# FAIO2.net
KiCad netlist of a schematic drawn in EAGLE
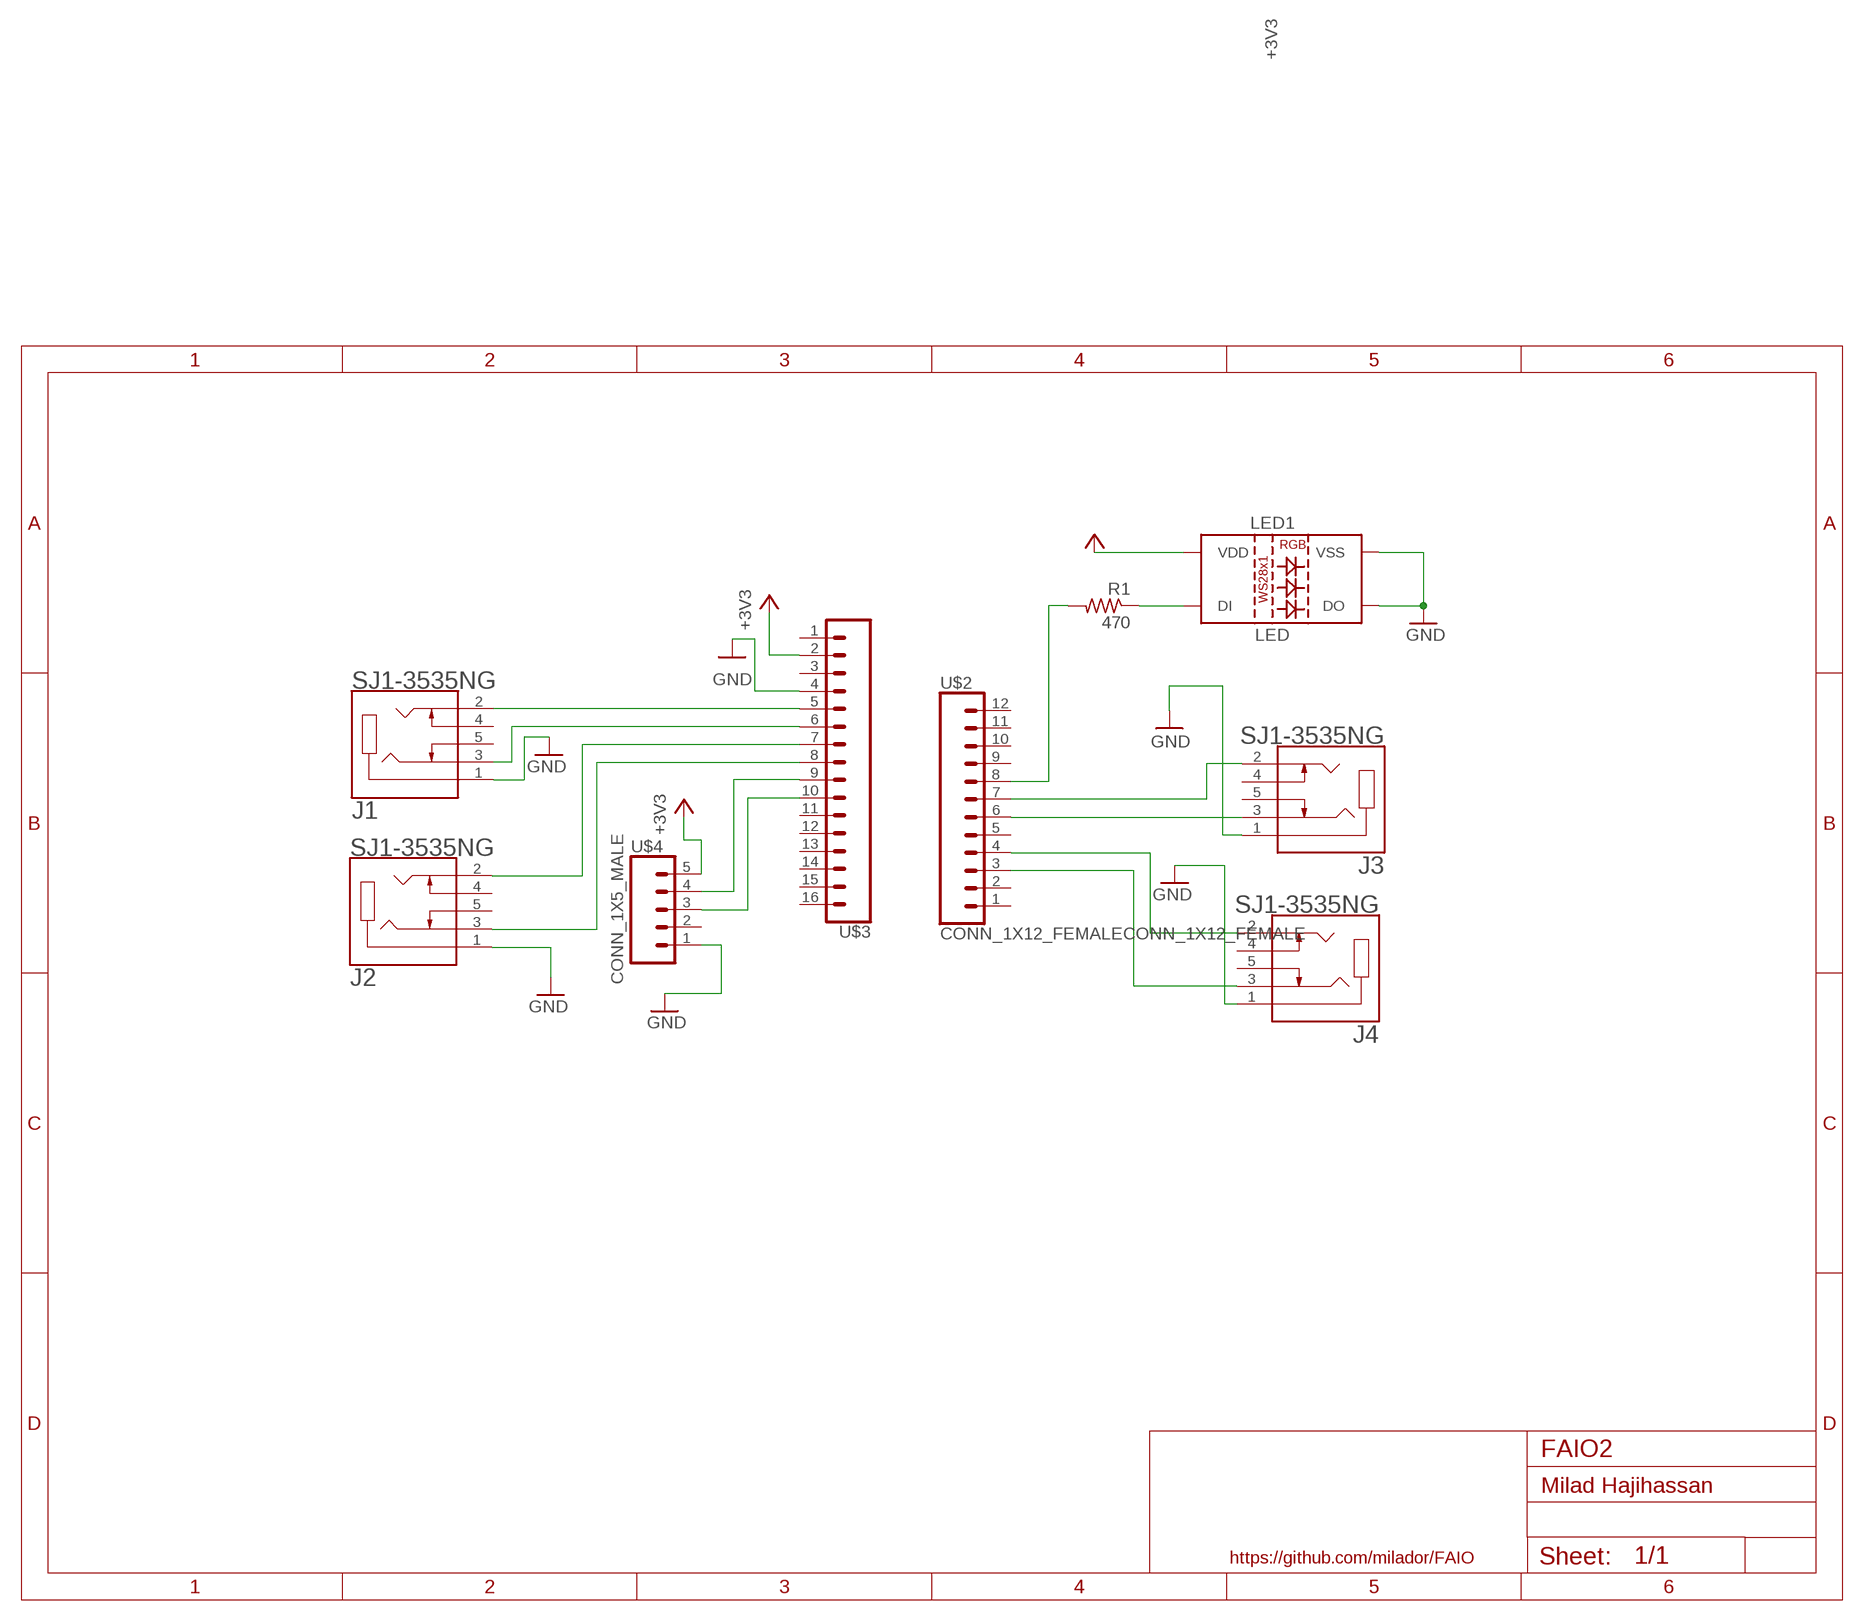
[diagram p0: schematic, sheet 1]

(export (version "E")
  (design (tool "Eeschema 10.0.6"))
  (components
    (comp (ref "J1")
      (value "SJ1-3535NG")
      (footprint "eagle-import:CUI_SJ1-3535NG")
      (fields (field (name "MANUFACTURER") "CUI"))
      (libsource (lib "eagle-import") (part "SJ1-3535NG"))
    )
    (comp (ref "J2")
      (value "SJ1-3535NG")
      (footprint "eagle-import:CUI_SJ1-3535NG")
      (fields (field (name "MANUFACTURER") "CUI"))
      (libsource (lib "eagle-import") (part "SJ1-3535NG"))
    )
    (comp (ref "J3")
      (value "SJ1-3535NG")
      (footprint "eagle-import:CUI_SJ1-3535NG")
      (fields (field (name "MANUFACTURER") "CUI"))
      (libsource (lib "eagle-import") (part "SJ1-3535NG"))
    )
    (comp (ref "J4")
      (value "SJ1-3535NG")
      (footprint "eagle-import:CUI_SJ1-3535NG")
      (fields (field (name "MANUFACTURER") "CUI"))
      (libsource (lib "eagle-import") (part "SJ1-3535NG"))
    )
    (comp (ref "LED1")
      (value "LED")
      (footprint "eagle-import:NEOPIXELS-5MM")
      (libsource (lib "eagle-import") (part "NEOPIXELS-5MM"))
    )
    (comp (ref "R1")
      (value "470")
      (footprint "eagle-import:0204_7")
      (libsource (lib "eagle-import") (part "R-US_0204/7"))
    )
    (comp (ref "U$2")
      (value "CONN_1X12_FEMALECONN_1X12_FEMALE")
      (footprint "eagle-import:CONN_1X12")
      (libsource (lib "eagle-import") (part "CONN_1X12_FEMALECONN_1X12_FEMALE"))
    )
    (comp (ref "U$3")
      (value "CONN_1X16_FEMALECONN_1X16_FEMALE")
      (footprint "eagle-import:CONN_1X16")
      (libsource (lib "eagle-import") (part "CONN_1X16_FEMALECONN_1X16_FEMALE"))
    )
    (comp (ref "U$4")
      (value "CONN_1X5_MALE")
      (footprint "eagle-import:CONN_1X5")
      (libsource (lib "eagle-import") (part "CONN_1X5_MALE"))
    )
  )
  (nets
    (net (code "1") (name "+3V3") (class "Default")
      (node (ref "LED1") (pin "2") (pinfunction "VDD_2") (pintype "bidirectional"))
      (node (ref "U$3") (pin "2") (pinfunction "2_2") (pintype "passive"))
      (node (ref "U$4") (pin "5") (pinfunction "5_5") (pintype "passive"))
    )
    (net (code "2") (name "GND") (class "Default")
      (node (ref "J1") (pin "1") (pinfunction "1_1") (pintype "passive"))
      (node (ref "J2") (pin "1") (pinfunction "1_1") (pintype "passive"))
      (node (ref "J3") (pin "1") (pinfunction "1_1") (pintype "passive"))
      (node (ref "J4") (pin "1") (pinfunction "1_1") (pintype "passive"))
      (node (ref "LED1") (pin "3") (pinfunction "VSS_3") (pintype "bidirectional"))
      (node (ref "LED1") (pin "4") (pinfunction "DO_4") (pintype "bidirectional"))
      (node (ref "U$3") (pin "4") (pinfunction "4_4") (pintype "passive"))
      (node (ref "U$4") (pin "1") (pinfunction "1_1") (pintype "passive"))
    )
    (net (code "3") (name "Net-(J1-Pad2)") (class "Default")
      (node (ref "J1") (pin "2") (pinfunction "2_2") (pintype "passive"))
      (node (ref "U$3") (pin "5") (pinfunction "5_5") (pintype "passive"))
    )
    (net (code "4") (name "Net-(J1-Pad3)") (class "Default")
      (node (ref "J1") (pin "3") (pinfunction "3_3") (pintype "passive"))
      (node (ref "U$3") (pin "6") (pinfunction "6_6") (pintype "passive"))
    )
    (net (code "5") (name "Net-(J2-Pad2)") (class "Default")
      (node (ref "J2") (pin "2") (pinfunction "2_2") (pintype "passive"))
      (node (ref "U$3") (pin "7") (pinfunction "7_7") (pintype "passive"))
    )
    (net (code "6") (name "Net-(J2-Pad3)") (class "Default")
      (node (ref "J2") (pin "3") (pinfunction "3_3") (pintype "passive"))
      (node (ref "U$3") (pin "8") (pinfunction "8_8") (pintype "passive"))
    )
    (net (code "7") (name "Net-(J3-Pad2)") (class "Default")
      (node (ref "J3") (pin "2") (pinfunction "2_2") (pintype "passive"))
      (node (ref "U$2") (pin "7") (pinfunction "7_7") (pintype "passive"))
    )
    (net (code "8") (name "Net-(J3-Pad3)") (class "Default")
      (node (ref "J3") (pin "3") (pinfunction "3_3") (pintype "passive"))
      (node (ref "U$2") (pin "6") (pinfunction "6_6") (pintype "passive"))
    )
    (net (code "9") (name "Net-(J4-Pad2)") (class "Default")
      (node (ref "J4") (pin "2") (pinfunction "2_2") (pintype "passive"))
      (node (ref "U$2") (pin "4") (pinfunction "4_4") (pintype "passive"))
    )
    (net (code "10") (name "Net-(J4-Pad3)") (class "Default")
      (node (ref "J4") (pin "3") (pinfunction "3_3") (pintype "passive"))
      (node (ref "U$2") (pin "3") (pinfunction "3_3") (pintype "passive"))
    )
    (net (code "11") (name "Net-(LED1-DI)") (class "Default")
      (node (ref "LED1") (pin "1") (pinfunction "DI_1") (pintype "bidirectional"))
      (node (ref "R1") (pin "1") (pinfunction "1_1") (pintype "passive"))
    )
    (net (code "12") (name "Net-(R1-Pad2)") (class "Default")
      (node (ref "R1") (pin "2") (pinfunction "2_2") (pintype "passive"))
      (node (ref "U$2") (pin "8") (pinfunction "8_8") (pintype "passive"))
    )
    (net (code "13") (name "Net-(U$3-Pad9)") (class "Default")
      (node (ref "U$3") (pin "9") (pinfunction "9_9") (pintype "passive"))
      (node (ref "U$4") (pin "4") (pinfunction "4_4") (pintype "passive"))
    )
    (net (code "14") (name "Net-(U$3-Pad10)") (class "Default")
      (node (ref "U$3") (pin "10") (pinfunction "10_10") (pintype "passive"))
      (node (ref "U$4") (pin "3") (pinfunction "3_3") (pintype "passive"))
    )
    (net (code "15") (name "unconnected-(J1-Pad4)") (class "Default")
      (node (ref "J1") (pin "4") (pinfunction "4_4") (pintype "passive"))
    )
    (net (code "16") (name "unconnected-(J1-Pad5)") (class "Default")
      (node (ref "J1") (pin "5") (pinfunction "5_5") (pintype "passive"))
    )
    (net (code "17") (name "unconnected-(J2-Pad4)") (class "Default")
      (node (ref "J2") (pin "4") (pinfunction "4_4") (pintype "passive"))
    )
    (net (code "18") (name "unconnected-(J2-Pad5)") (class "Default")
      (node (ref "J2") (pin "5") (pinfunction "5_5") (pintype "passive"))
    )
    (net (code "19") (name "unconnected-(J3-Pad4)") (class "Default")
      (node (ref "J3") (pin "4") (pinfunction "4_4") (pintype "passive"))
    )
    (net (code "20") (name "unconnected-(J3-Pad5)") (class "Default")
      (node (ref "J3") (pin "5") (pinfunction "5_5") (pintype "passive"))
    )
    (net (code "21") (name "unconnected-(J4-Pad4)") (class "Default")
      (node (ref "J4") (pin "4") (pinfunction "4_4") (pintype "passive"))
    )
    (net (code "22") (name "unconnected-(J4-Pad5)") (class "Default")
      (node (ref "J4") (pin "5") (pinfunction "5_5") (pintype "passive"))
    )
    (net (code "23") (name "unconnected-(U$2-Pad1)") (class "Default")
      (node (ref "U$2") (pin "1") (pinfunction "1_1") (pintype "passive"))
    )
    (net (code "24") (name "unconnected-(U$2-Pad2)") (class "Default")
      (node (ref "U$2") (pin "2") (pinfunction "2_2") (pintype "passive"))
    )
    (net (code "25") (name "unconnected-(U$2-Pad5)") (class "Default")
      (node (ref "U$2") (pin "5") (pinfunction "5_5") (pintype "passive"))
    )
    (net (code "26") (name "unconnected-(U$2-Pad9)") (class "Default")
      (node (ref "U$2") (pin "9") (pinfunction "9_9") (pintype "passive"))
    )
    (net (code "27") (name "unconnected-(U$2-Pad10)") (class "Default")
      (node (ref "U$2") (pin "10") (pinfunction "10_10") (pintype "passive"))
    )
    (net (code "28") (name "unconnected-(U$2-Pad11)") (class "Default")
      (node (ref "U$2") (pin "11") (pinfunction "11_11") (pintype "passive"))
    )
    (net (code "29") (name "unconnected-(U$2-Pad12)") (class "Default")
      (node (ref "U$2") (pin "12") (pinfunction "12_12") (pintype "passive"))
    )
    (net (code "30") (name "unconnected-(U$3-Pad1)") (class "Default")
      (node (ref "U$3") (pin "1") (pinfunction "1_1") (pintype "passive"))
    )
    (net (code "31") (name "unconnected-(U$3-Pad3)") (class "Default")
      (node (ref "U$3") (pin "3") (pinfunction "3_3") (pintype "passive"))
    )
    (net (code "32") (name "unconnected-(U$3-Pad11)") (class "Default")
      (node (ref "U$3") (pin "11") (pinfunction "11_11") (pintype "passive"))
    )
    (net (code "33") (name "unconnected-(U$3-Pad12)") (class "Default")
      (node (ref "U$3") (pin "12") (pinfunction "12_12") (pintype "passive"))
    )
    (net (code "34") (name "unconnected-(U$3-Pad13)") (class "Default")
      (node (ref "U$3") (pin "13") (pinfunction "13_13") (pintype "passive"))
    )
    (net (code "35") (name "unconnected-(U$3-Pad14)") (class "Default")
      (node (ref "U$3") (pin "14") (pinfunction "14_14") (pintype "passive"))
    )
    (net (code "36") (name "unconnected-(U$3-Pad15)") (class "Default")
      (node (ref "U$3") (pin "15") (pinfunction "15_15") (pintype "passive"))
    )
    (net (code "37") (name "unconnected-(U$3-Pad16)") (class "Default")
      (node (ref "U$3") (pin "16") (pinfunction "16_16") (pintype "passive"))
    )
    (net (code "38") (name "unconnected-(U$4-Pad2)") (class "Default")
      (node (ref "U$4") (pin "2") (pinfunction "2_2") (pintype "passive"))
    )
  )
)
